# schematic.net
KiCad netlist of a schematic drawn in Altium Designer
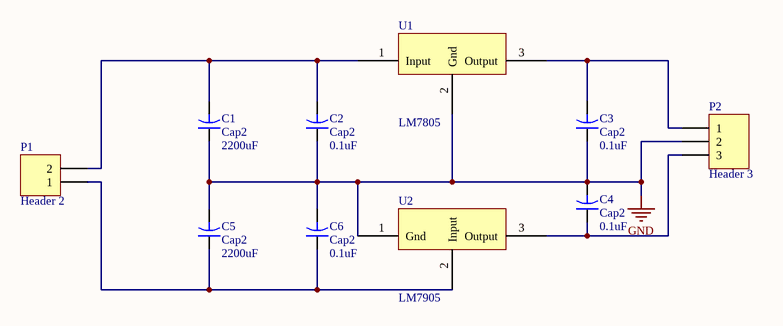
[diagram p0: schematic.SchDoc]

(export (version "E")
  (design (tool "Eeschema 10.0.6"))
  (components
    (comp (ref "C1")
      (value "Cap2")
      (footprint "CAPR5-4X5")
      (description "Capacitor")
      (fields (field (name "ALTIUM_VALUE") "2200uF") (field (name "PUBLISHER") "Altium Limited"))
      (libsource (lib "Miscellaneous Devices") (part "Cap2"))
    )
    (comp (ref "C2")
      (value "Cap2")
      (footprint "CAPR5-4X5")
      (description "Capacitor")
      (fields (field (name "ALTIUM_VALUE") "0.1uF") (field (name "PUBLISHER") "Altium Limited"))
      (libsource (lib "Miscellaneous Devices") (part "Cap2"))
    )
    (comp (ref "C3")
      (value "Cap2")
      (footprint "CAPR5-4X5")
      (description "Capacitor")
      (fields (field (name "ALTIUM_VALUE") "0.1uF") (field (name "PUBLISHER") "Altium Limited"))
      (libsource (lib "Miscellaneous Devices") (part "Cap2"))
    )
    (comp (ref "C4")
      (value "Cap2")
      (footprint "CAPR5-4X5")
      (description "Capacitor")
      (fields (field (name "ALTIUM_VALUE") "0.1uF") (field (name "PUBLISHER") "Altium Limited"))
      (libsource (lib "Miscellaneous Devices") (part "Cap2"))
    )
    (comp (ref "C5")
      (value "Cap2")
      (footprint "CAPR5-4X5")
      (description "Capacitor")
      (fields (field (name "ALTIUM_VALUE") "2200uF") (field (name "PUBLISHER") "Altium Limited"))
      (libsource (lib "Miscellaneous Devices") (part "Cap2"))
    )
    (comp (ref "C6")
      (value "Cap2")
      (footprint "CAPR5-4X5")
      (description "Capacitor")
      (fields (field (name "ALTIUM_VALUE") "0.1uF") (field (name "PUBLISHER") "Altium Limited"))
      (libsource (lib "Miscellaneous Devices") (part "Cap2"))
    )
    (comp (ref "P1")
      (value "Header 2")
      (footprint "HDR1X2")
      (description "Header, 2-Pin")
      (fields (field (name "PUBLISHER") "Altium Limited"))
      (libsource (lib "Miscellaneous Connectors") (part "Header 2"))
    )
    (comp (ref "P2")
      (value "Header 3")
      (footprint "HDR1X3")
      (description "Header, 3-Pin")
      (fields (field (name "PUBLISHER") "Altium Limited"))
      (libsource (lib "Miscellaneous Connectors") (part "Header 3"))
    )
    (comp (ref "U1") (value "LM7805") (footprint "LM7805") (libsource (lib "LM7805sch") (part "LM7805")))
    (comp (ref "U2") (value "LM7905") (footprint "LM7905") (libsource (lib "LM7905sch") (part "LM7905")))
  )
  (nets
    (net (code "1") (name "GND") (class "Default")
      (node (ref "C1") (pin "1") (pinfunction "1_1") (pintype "passive"))
      (node (ref "C2") (pin "1") (pinfunction "1_1") (pintype "passive"))
      (node (ref "C3") (pin "1") (pinfunction "1_1") (pintype "passive"))
      (node (ref "C4") (pin "2") (pinfunction "2_2") (pintype "passive"))
      (node (ref "C5") (pin "2") (pinfunction "2_2") (pintype "passive"))
      (node (ref "C6") (pin "2") (pinfunction "2_2") (pintype "passive"))
      (node (ref "P2") (pin "2") (pinfunction "2_2") (pintype "passive"))
      (node (ref "U1") (pin "2") (pinfunction "Gnd_2") (pintype "passive"))
      (node (ref "U2") (pin "1") (pinfunction "Gnd_1") (pintype "passive"))
    )
    (net (code "2") (name "Net-(U1-Input)") (class "Default")
      (node (ref "C1") (pin "2") (pinfunction "2_2") (pintype "passive"))
      (node (ref "C2") (pin "2") (pinfunction "2_2") (pintype "passive"))
      (node (ref "P1") (pin "2") (pinfunction "2_2") (pintype "passive"))
      (node (ref "U1") (pin "1") (pinfunction "Input_1") (pintype "passive"))
    )
    (net (code "3") (name "Net-(U1-Output)") (class "Default")
      (node (ref "C3") (pin "2") (pinfunction "2_2") (pintype "passive"))
      (node (ref "P2") (pin "1") (pinfunction "1_1") (pintype "passive"))
      (node (ref "U1") (pin "3") (pinfunction "Output_3") (pintype "passive"))
    )
    (net (code "4") (name "Net-(U2-Input)") (class "Default")
      (node (ref "C5") (pin "1") (pinfunction "1_1") (pintype "passive"))
      (node (ref "C6") (pin "1") (pinfunction "1_1") (pintype "passive"))
      (node (ref "P1") (pin "1") (pinfunction "1_1") (pintype "passive"))
      (node (ref "U2") (pin "2") (pinfunction "Input_2") (pintype "passive"))
    )
    (net (code "5") (name "Net-(U2-Output)") (class "Default")
      (node (ref "C4") (pin "1") (pinfunction "1_1") (pintype "passive"))
      (node (ref "P2") (pin "3") (pinfunction "3_3") (pintype "passive"))
      (node (ref "U2") (pin "3") (pinfunction "Output_3") (pintype "passive"))
    )
  )
)
